# V1.net
KiCad netlist of a schematic drawn in Altium Designer
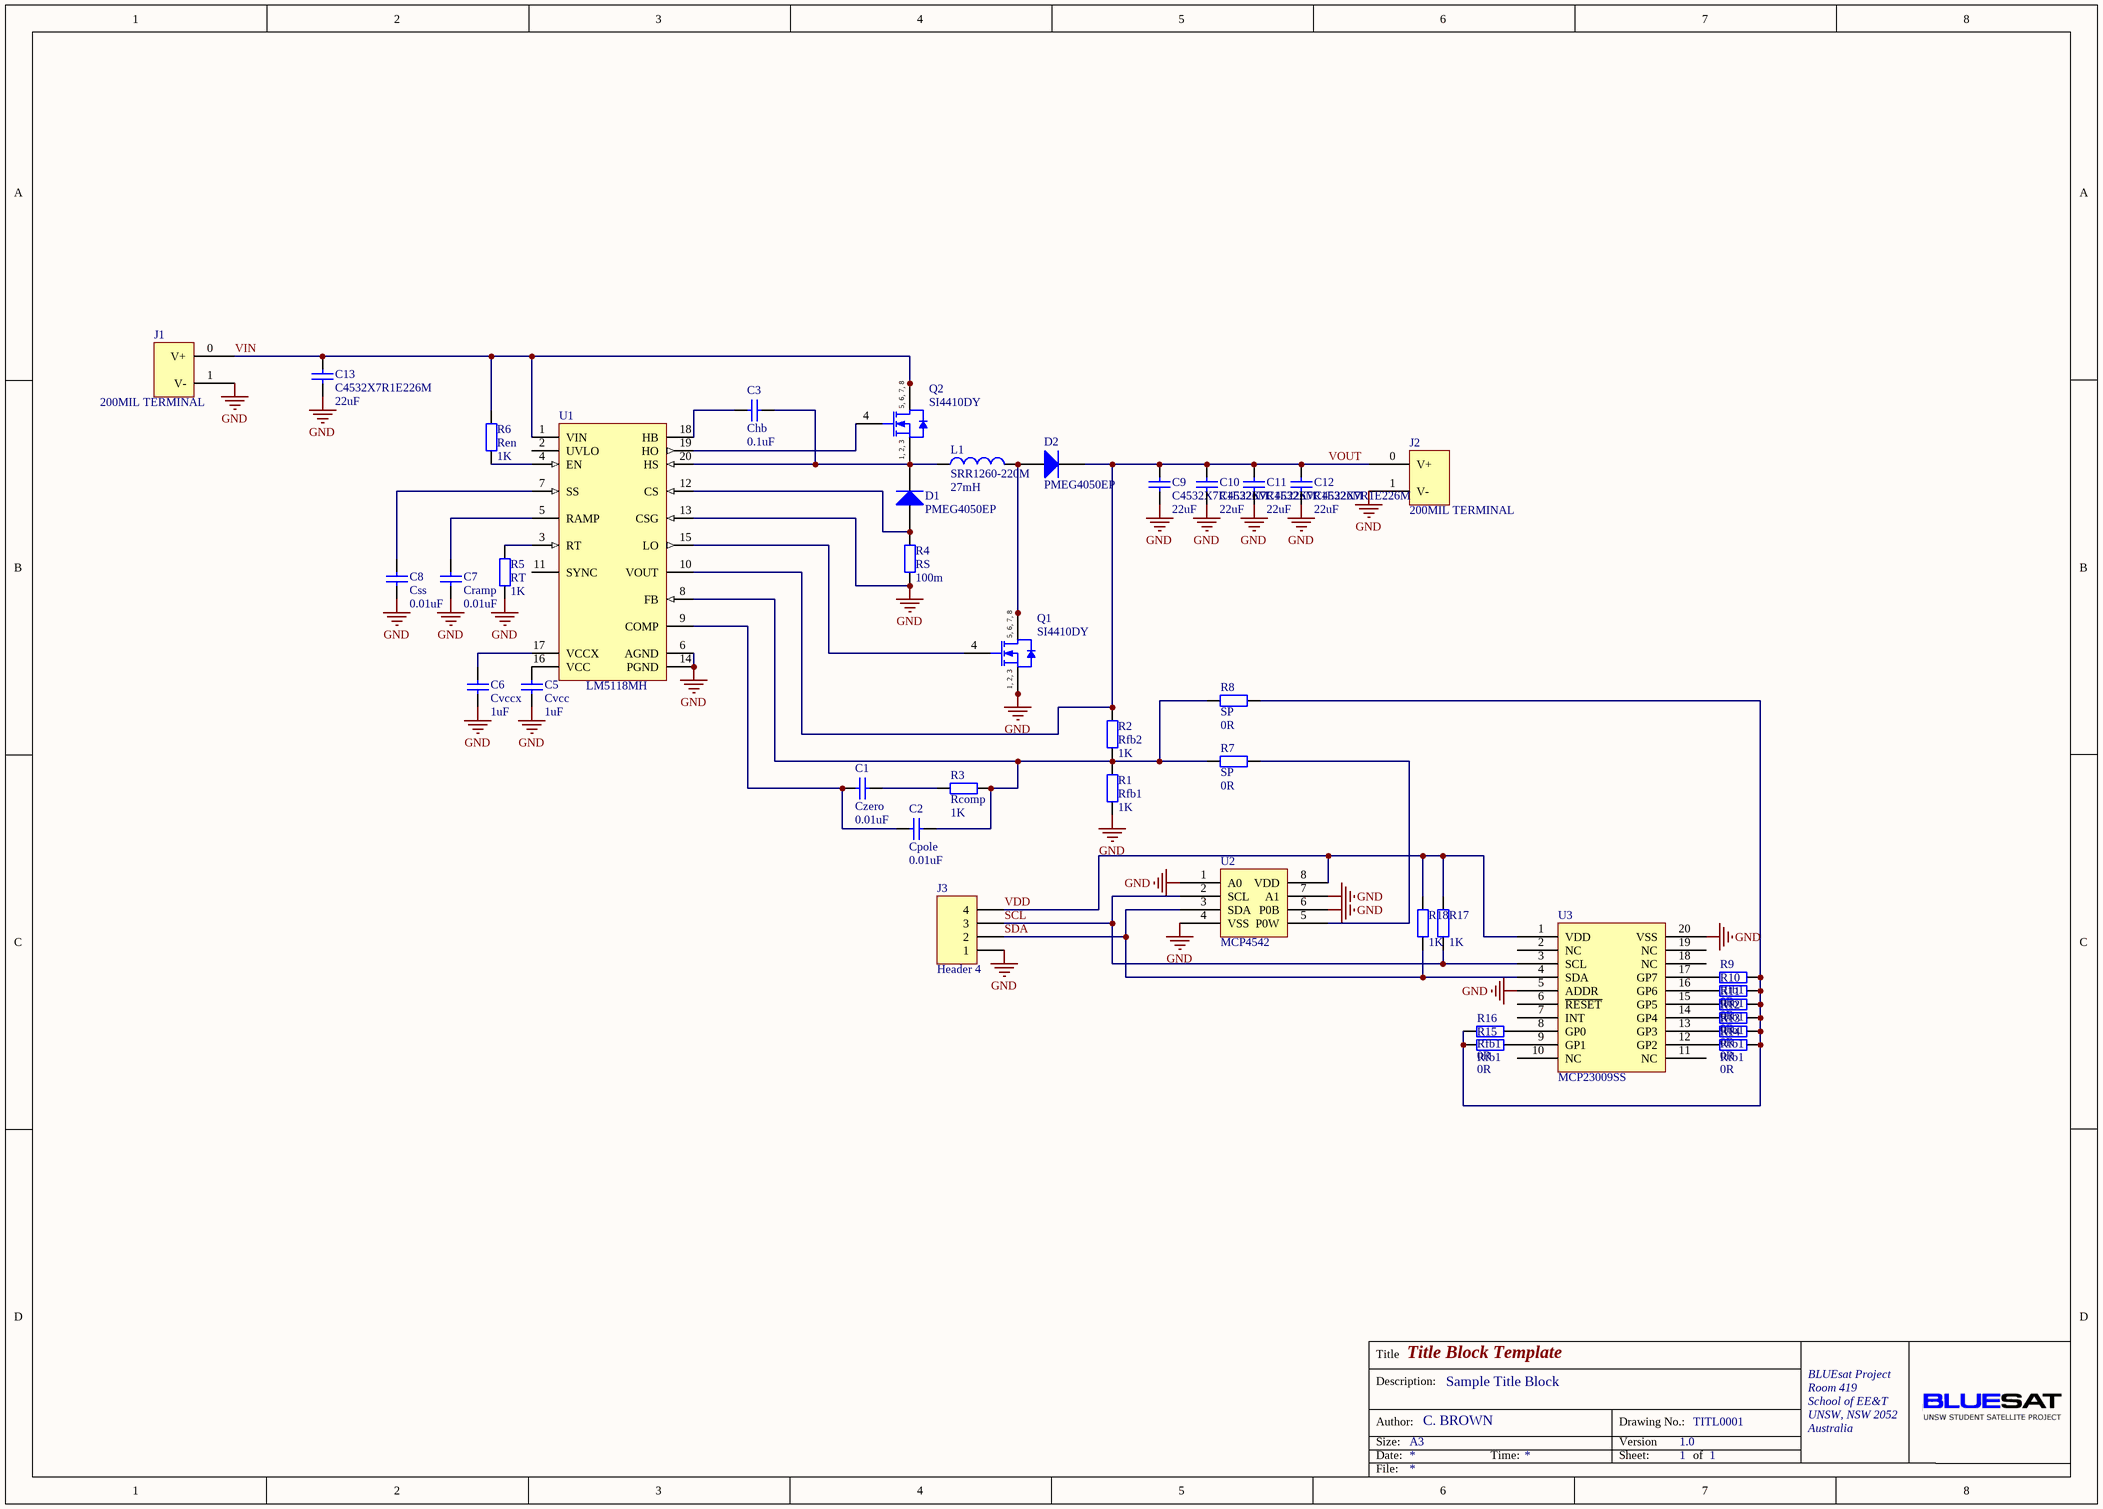
[diagram p0: V1.SchDoc]

(export (version "E")
  (design (tool "Eeschema 10.0.6"))
  (components
    (comp (ref "C1")
      (value "Czero")
      (footprint "R0805M")
      (description "Capacitor")
      (fields (field (name "ALTIUM_VALUE") "0.01uF") (field (name "PUBLISHER") "Altium Limited"))
      (libsource (lib "Miscellaneous Devices") (part "Cap"))
    )
    (comp (ref "C2")
      (value "Cpole")
      (footprint "R0805M")
      (description "Capacitor")
      (fields (field (name "ALTIUM_VALUE") "0.01uF") (field (name "PUBLISHER") "Altium Limited"))
      (libsource (lib "Miscellaneous Devices") (part "Cap"))
    )
    (comp (ref "C3")
      (value "Chb")
      (footprint "R0805M")
      (description "Capacitor")
      (fields (field (name "ALTIUM_VALUE") "0.1uF") (field (name "PUBLISHER") "Altium Limited"))
      (libsource (lib "Miscellaneous Devices") (part "Cap"))
    )
    (comp (ref "C5")
      (value "Cvcc")
      (footprint "R0805M")
      (description "Capacitor")
      (fields (field (name "ALTIUM_VALUE") "1uF") (field (name "PUBLISHER") "Altium Limited"))
      (libsource (lib "Miscellaneous Devices") (part "Cap"))
    )
    (comp (ref "C6")
      (value "Cvccx")
      (footprint "R0805M")
      (description "Capacitor")
      (fields (field (name "ALTIUM_VALUE") "1uF") (field (name "PUBLISHER") "Altium Limited"))
      (libsource (lib "Miscellaneous Devices") (part "Cap"))
    )
    (comp (ref "C7")
      (value "Cramp")
      (footprint "R0805M")
      (description "Capacitor")
      (fields (field (name "ALTIUM_VALUE") "0.01uF") (field (name "PUBLISHER") "Altium Limited"))
      (libsource (lib "Miscellaneous Devices") (part "Cap"))
    )
    (comp (ref "C8")
      (value "Css")
      (footprint "R0805M")
      (description "Capacitor")
      (fields (field (name "ALTIUM_VALUE") "0.01uF") (field (name "PUBLISHER") "Altium Limited"))
      (libsource (lib "Miscellaneous Devices") (part "Cap"))
    )
    (comp (ref "C9")
      (value "C4532X7R1E226M")
      (footprint "R1812M")
      (description "Capacitor")
      (fields (field (name "ALTIUM_VALUE") "22uF") (field (name "PUBLISHER") "Altium Limited"))
      (libsource (lib "Miscellaneous Devices") (part "Cap"))
    )
    (comp (ref "C10")
      (value "C4532X7R1E226M")
      (footprint "R1812M")
      (description "Capacitor")
      (fields (field (name "ALTIUM_VALUE") "22uF") (field (name "PUBLISHER") "Altium Limited"))
      (libsource (lib "Miscellaneous Devices") (part "Cap"))
    )
    (comp (ref "C11")
      (value "C4532X7R1E226M")
      (footprint "R1812M")
      (description "Capacitor")
      (fields (field (name "ALTIUM_VALUE") "22uF") (field (name "PUBLISHER") "Altium Limited"))
      (libsource (lib "Miscellaneous Devices") (part "Cap"))
    )
    (comp (ref "C12")
      (value "C4532X7R1E226M")
      (footprint "R1812M")
      (description "Capacitor")
      (fields (field (name "ALTIUM_VALUE") "22uF") (field (name "PUBLISHER") "Altium Limited"))
      (libsource (lib "Miscellaneous Devices") (part "Cap"))
    )
    (comp (ref "C13")
      (value "C4532X7R1E226M")
      (footprint "R1812M")
      (description "Capacitor")
      (fields (field (name "ALTIUM_VALUE") "22uF") (field (name "PUBLISHER") "Altium Limited"))
      (libsource (lib "Miscellaneous Devices") (part "Cap"))
    )
    (comp (ref "D1")
      (value "PMEG4050EP")
      (footprint "SOD128M")
      (description "Default Diode")
      (fields (field (name "PUBLISHER") "Altium Limited"))
      (libsource (lib "Miscellaneous Devices") (part "Diode"))
    )
    (comp (ref "D2")
      (value "PMEG4050EP")
      (footprint "SOD128M")
      (description "Default Diode")
      (fields (field (name "PUBLISHER") "Altium Limited"))
      (libsource (lib "Miscellaneous Devices") (part "Diode"))
    )
    (comp (ref "J1")
      (value "200MIL TERMINAL")
      (footprint "200MIL TERMINAL")
      (libsource (lib "VarReg") (part "200MIL TERMINAL"))
    )
    (comp (ref "J2")
      (value "200MIL TERMINAL")
      (footprint "200MIL TERMINAL")
      (libsource (lib "") (part "200MIL TERMINAL_1"))
    )
    (comp (ref "J3")
      (value "Header 4")
      (footprint "HDR1X4")
      (description "Header, 4-Pin")
      (fields (field (name "PUBLISHER") "Altium Limited"))
      (libsource (lib "Miscellaneous Connectors") (part "Header 4"))
    )
    (comp (ref "L1")
      (value "SRR1260-220M")
      (footprint "SRR1260M")
      (description "Inductor")
      (fields (field (name "ALTIUM_VALUE") "27mH") (field (name "PUBLISHER") "Altium Limited"))
      (libsource (lib "Miscellaneous Devices") (part "Inductor"))
    )
    (comp (ref "Q1")
      (value "SI4410DY")
      (footprint "SO-8_N")
      (description "N-Channel 30V (D-S)  MOSFET")
      (fields (field (name "PUBLISHER") "Altium Limited"))
      (libsource (lib "Vishay Siliconix Discrete MOSFET") (part "SI4410DY"))
    )
    (comp (ref "Q2")
      (value "SI4410DY")
      (footprint "SO-8_N")
      (description "N-Channel 30V (D-S)  MOSFET")
      (fields (field (name "PUBLISHER") "Altium Limited"))
      (libsource (lib "Vishay Siliconix Discrete MOSFET") (part "SI4410DY"))
    )
    (comp (ref "R1")
      (value "Rfb1")
      (footprint "R0805M")
      (description "Resistor")
      (fields (field (name "ALTIUM_VALUE") "1K") (field (name "PUBLISHER") "Altium Limited"))
      (libsource (lib "") (part "Res2_2"))
    )
    (comp (ref "R2")
      (value "Rfb2")
      (footprint "R0805M")
      (description "Resistor")
      (fields (field (name "ALTIUM_VALUE") "1K") (field (name "PUBLISHER") "Altium Limited"))
      (libsource (lib "") (part "Res2_2"))
    )
    (comp (ref "R3")
      (value "Rcomp")
      (footprint "R0805M")
      (description "Resistor")
      (fields (field (name "ALTIUM_VALUE") "1K") (field (name "PUBLISHER") "Altium Limited"))
      (libsource (lib "") (part "Res2_1"))
    )
    (comp (ref "R4")
      (value "RS")
      (footprint "R0805M")
      (description "Resistor")
      (fields (field (name "ALTIUM_VALUE") "100m") (field (name "PUBLISHER") "Altium Limited"))
      (libsource (lib "") (part "Res2_2"))
    )
    (comp (ref "R5")
      (value "RT")
      (footprint "R0805M")
      (description "Resistor")
      (fields (field (name "ALTIUM_VALUE") "1K") (field (name "PUBLISHER") "Altium Limited"))
      (libsource (lib "") (part "Res2_2"))
    )
    (comp (ref "R6")
      (value "Ren")
      (footprint "R0805M")
      (description "Resistor")
      (fields (field (name "ALTIUM_VALUE") "1K") (field (name "PUBLISHER") "Altium Limited"))
      (libsource (lib "") (part "Res2_2"))
    )
    (comp (ref "R7")
      (value "SP")
      (footprint "R0805M")
      (description "Resistor")
      (fields (field (name "ALTIUM_VALUE") "0R") (field (name "PUBLISHER") "Altium Limited"))
      (libsource (lib "Miscellaneous Devices") (part "Res2"))
    )
    (comp (ref "R8")
      (value "SP")
      (footprint "R0805M")
      (description "Resistor")
      (fields (field (name "ALTIUM_VALUE") "0R") (field (name "PUBLISHER") "Altium Limited"))
      (libsource (lib "Miscellaneous Devices") (part "Res2"))
    )
    (comp (ref "R9")
      (value "Rfb1")
      (footprint "R0805M")
      (description "Resistor")
      (fields (field (name "ALTIUM_VALUE") "0R") (field (name "PUBLISHER") "Altium Limited"))
      (libsource (lib "Miscellaneous Devices") (part "Res2"))
    )
    (comp (ref "R10")
      (value "Rfb1")
      (footprint "R0805M")
      (description "Resistor")
      (fields (field (name "ALTIUM_VALUE") "0R") (field (name "PUBLISHER") "Altium Limited"))
      (libsource (lib "Miscellaneous Devices") (part "Res2"))
    )
    (comp (ref "R11")
      (value "Rfb1")
      (footprint "R0805M")
      (description "Resistor")
      (fields (field (name "ALTIUM_VALUE") "0R") (field (name "PUBLISHER") "Altium Limited"))
      (libsource (lib "Miscellaneous Devices") (part "Res2"))
    )
    (comp (ref "R12")
      (value "Rfb1")
      (footprint "R0805M")
      (description "Resistor")
      (fields (field (name "ALTIUM_VALUE") "0R") (field (name "PUBLISHER") "Altium Limited"))
      (libsource (lib "Miscellaneous Devices") (part "Res2"))
    )
    (comp (ref "R13")
      (value "Rfb1")
      (footprint "R0805M")
      (description "Resistor")
      (fields (field (name "ALTIUM_VALUE") "0R") (field (name "PUBLISHER") "Altium Limited"))
      (libsource (lib "Miscellaneous Devices") (part "Res2"))
    )
    (comp (ref "R14")
      (value "Rfb1")
      (footprint "R0805M")
      (description "Resistor")
      (fields (field (name "ALTIUM_VALUE") "0R") (field (name "PUBLISHER") "Altium Limited"))
      (libsource (lib "Miscellaneous Devices") (part "Res2"))
    )
    (comp (ref "R15")
      (value "Rfb1")
      (footprint "R0805M")
      (description "Resistor")
      (fields (field (name "ALTIUM_VALUE") "0R") (field (name "PUBLISHER") "Altium Limited"))
      (libsource (lib "Miscellaneous Devices") (part "Res2"))
    )
    (comp (ref "R16")
      (value "Rfb1")
      (footprint "R0805M")
      (description "Resistor")
      (fields (field (name "ALTIUM_VALUE") "0R") (field (name "PUBLISHER") "Altium Limited"))
      (libsource (lib "Miscellaneous Devices") (part "Res2"))
    )
    (comp (ref "R17")
      (value "1K")
      (footprint "R0805M")
      (description "Resistor")
      (fields (field (name "PUBLISHER") "Altium Limited"))
      (libsource (lib "") (part "Res2_2"))
    )
    (comp (ref "R18")
      (value "1K")
      (footprint "R0805M")
      (description "Resistor")
      (fields (field (name "PUBLISHER") "Altium Limited"))
      (libsource (lib "") (part "Res2_2"))
    )
    (comp (ref "U1")
      (value "LM5118MH")
      (footprint "MXA20A_N")
      (description "Wide Voltage Range Buck-Boost Controller")
      (fields
        (field (name "MANUFACTURER") "National Semiconductor")
        (field (name "DIGIKEYPARTNUMBER") "LM5118MH-ND")
        (field (name "PUBLISHER") "Altium Limited")
      )
      (libsource (lib "NSC Switcher") (part "LM5118MH"))
    )
    (comp (ref "U2")
      (value "MCP4542")
      (footprint "Zetex Discrete MOSFET:MSOP8")
      (libsource (lib "VarReg") (part "MCP4542"))
    )
    (comp (ref "U3")
      (value "MCP23009SS")
      (footprint "SSOP20_M")
      (libsource (lib "VarReg") (part "MCP23009SS"))
    )
  )
  (nets
    (net (code "1") (name "/SCL") (class "Default")
      (node (ref "J3") (pin "3") (pinfunction "3_3") (pintype "passive"))
      (node (ref "R17") (pin "1") (pinfunction "1_1") (pintype "passive"))
      (node (ref "U2") (pin "2") (pinfunction "SCL_2") (pintype "passive"))
      (node (ref "U3") (pin "3") (pinfunction "SCL_3") (pintype "passive"))
    )
    (net (code "2") (name "/SDA") (class "Default")
      (node (ref "J3") (pin "2") (pinfunction "2_2") (pintype "passive"))
      (node (ref "R18") (pin "1") (pinfunction "1_1") (pintype "passive"))
      (node (ref "U2") (pin "3") (pinfunction "SDA_3") (pintype "passive"))
      (node (ref "U3") (pin "4") (pinfunction "SDA_4") (pintype "passive"))
    )
    (net (code "3") (name "/VDD") (class "Default")
      (node (ref "J3") (pin "4") (pinfunction "4_4") (pintype "passive"))
      (node (ref "R17") (pin "2") (pinfunction "2_2") (pintype "passive"))
      (node (ref "R18") (pin "2") (pinfunction "2_2") (pintype "passive"))
      (node (ref "U2") (pin "8") (pinfunction "VDD_8") (pintype "passive"))
      (node (ref "U3") (pin "1") (pinfunction "VDD_1") (pintype "passive"))
    )
    (net (code "4") (name "/VIN") (class "Default")
      (node (ref "C13") (pin "2") (pinfunction "2_2") (pintype "passive"))
      (node (ref "J1") (pin "0") (pinfunction "V+_0") (pintype "passive"))
      (node (ref "Q2") (pin "5") (pinfunction "D_5") (pintype "passive"))
      (node (ref "Q2") (pin "6") (pinfunction "D_6") (pintype "passive"))
      (node (ref "Q2") (pin "7") (pinfunction "D_7") (pintype "passive"))
      (node (ref "Q2") (pin "8") (pinfunction "D_8") (pintype "passive"))
      (node (ref "R6") (pin "2") (pinfunction "2_2") (pintype "passive"))
      (node (ref "U1") (pin "1") (pinfunction "VIN_1") (pintype "power_in"))
    )
    (net (code "5") (name "/VOUT") (class "Default")
      (node (ref "C10") (pin "2") (pinfunction "2_2") (pintype "passive"))
      (node (ref "C11") (pin "2") (pinfunction "2_2") (pintype "passive"))
      (node (ref "C12") (pin "2") (pinfunction "2_2") (pintype "passive"))
      (node (ref "C9") (pin "2") (pinfunction "2_2") (pintype "passive"))
      (node (ref "D2") (pin "2") (pinfunction "K_2") (pintype "passive"))
      (node (ref "J2") (pin "0") (pinfunction "V+_0") (pintype "passive"))
      (node (ref "R2") (pin "2") (pinfunction "2_2") (pintype "passive"))
      (node (ref "U1") (pin "10") (pinfunction "VOUT_10") (pintype "passive"))
    )
    (net (code "6") (name "GND") (class "Default")
      (node (ref "C10") (pin "1") (pinfunction "1_1") (pintype "passive"))
      (node (ref "C11") (pin "1") (pinfunction "1_1") (pintype "passive"))
      (node (ref "C12") (pin "1") (pinfunction "1_1") (pintype "passive"))
      (node (ref "C13") (pin "1") (pinfunction "1_1") (pintype "passive"))
      (node (ref "C5") (pin "1") (pinfunction "1_1") (pintype "passive"))
      (node (ref "C6") (pin "1") (pinfunction "1_1") (pintype "passive"))
      (node (ref "C7") (pin "1") (pinfunction "1_1") (pintype "passive"))
      (node (ref "C8") (pin "1") (pinfunction "1_1") (pintype "passive"))
      (node (ref "C9") (pin "1") (pinfunction "1_1") (pintype "passive"))
      (node (ref "J1") (pin "1") (pinfunction "V-_1") (pintype "passive"))
      (node (ref "J2") (pin "1") (pinfunction "V-_1") (pintype "passive"))
      (node (ref "J3") (pin "1") (pinfunction "1_1") (pintype "passive"))
      (node (ref "Q1") (pin "1") (pinfunction "S_1") (pintype "passive"))
      (node (ref "Q1") (pin "2") (pinfunction "S_2") (pintype "passive"))
      (node (ref "Q1") (pin "3") (pinfunction "S_3") (pintype "passive"))
      (node (ref "R1") (pin "1") (pinfunction "1_1") (pintype "passive"))
      (node (ref "R4") (pin "1") (pinfunction "1_1") (pintype "passive"))
      (node (ref "R5") (pin "1") (pinfunction "1_1") (pintype "passive"))
      (node (ref "U1") (pin "13") (pinfunction "CSG_13") (pintype "input"))
      (node (ref "U1") (pin "14") (pinfunction "PGND_14") (pintype "power_in"))
      (node (ref "U1") (pin "6") (pinfunction "AGND_6") (pintype "power_in"))
      (node (ref "U2") (pin "1") (pinfunction "A0_1") (pintype "passive"))
      (node (ref "U2") (pin "4") (pinfunction "VSS_4") (pintype "passive"))
      (node (ref "U2") (pin "6") (pinfunction "P0B_6") (pintype "passive"))
      (node (ref "U2") (pin "7") (pinfunction "A1_7") (pintype "passive"))
      (node (ref "U3") (pin "20") (pinfunction "VSS_20") (pintype "passive"))
      (node (ref "U3") (pin "5") (pinfunction "ADDR_5") (pintype "passive"))
    )
    (net (code "7") (name "Net-(C1-Pad2)") (class "Default")
      (node (ref "C1") (pin "2") (pinfunction "2_2") (pintype "passive"))
      (node (ref "R3") (pin "1") (pinfunction "1_1") (pintype "passive"))
    )
    (net (code "8") (name "Net-(D1-A)") (class "Default")
      (node (ref "D1") (pin "1") (pinfunction "A_1") (pintype "passive"))
      (node (ref "R4") (pin "2") (pinfunction "2_2") (pintype "passive"))
      (node (ref "U1") (pin "12") (pinfunction "CS_12") (pintype "input"))
    )
    (net (code "9") (name "Net-(D1-K)") (class "Default")
      (node (ref "C3") (pin "2") (pinfunction "2_2") (pintype "passive"))
      (node (ref "D1") (pin "2") (pinfunction "K_2") (pintype "passive"))
      (node (ref "L1") (pin "1") (pinfunction "1_1") (pintype "passive"))
      (node (ref "Q2") (pin "1") (pinfunction "S_1") (pintype "passive"))
      (node (ref "Q2") (pin "2") (pinfunction "S_2") (pintype "passive"))
      (node (ref "Q2") (pin "3") (pinfunction "S_3") (pintype "passive"))
      (node (ref "U1") (pin "20") (pinfunction "HS_20") (pintype "input"))
    )
    (net (code "10") (name "Net-(D2-A)") (class "Default")
      (node (ref "D2") (pin "1") (pinfunction "A_1") (pintype "passive"))
      (node (ref "L1") (pin "2") (pinfunction "2_2") (pintype "passive"))
      (node (ref "Q1") (pin "5") (pinfunction "D_5") (pintype "passive"))
      (node (ref "Q1") (pin "6") (pinfunction "D_6") (pintype "passive"))
      (node (ref "Q1") (pin "7") (pinfunction "D_7") (pintype "passive"))
      (node (ref "Q1") (pin "8") (pinfunction "D_8") (pintype "passive"))
    )
    (net (code "11") (name "Net-(Q1-G)") (class "Default")
      (node (ref "Q1") (pin "4") (pinfunction "G_4") (pintype "passive"))
      (node (ref "U1") (pin "15") (pinfunction "LO_15") (pintype "output"))
    )
    (net (code "12") (name "Net-(Q2-G)") (class "Default")
      (node (ref "Q2") (pin "4") (pinfunction "G_4") (pintype "passive"))
      (node (ref "U1") (pin "19") (pinfunction "HO_19") (pintype "output"))
    )
    (net (code "13") (name "Net-(R10-Pad1)") (class "Default")
      (node (ref "R10") (pin "1") (pinfunction "1_1") (pintype "passive"))
      (node (ref "R11") (pin "1") (pinfunction "1_1") (pintype "passive"))
      (node (ref "R12") (pin "1") (pinfunction "1_1") (pintype "passive"))
      (node (ref "R13") (pin "1") (pinfunction "1_1") (pintype "passive"))
      (node (ref "R14") (pin "1") (pinfunction "1_1") (pintype "passive"))
      (node (ref "R15") (pin "2") (pinfunction "2_2") (pintype "passive"))
      (node (ref "R16") (pin "2") (pinfunction "2_2") (pintype "passive"))
      (node (ref "R8") (pin "1") (pinfunction "1_1") (pintype "passive"))
      (node (ref "R9") (pin "1") (pinfunction "1_1") (pintype "passive"))
    )
    (net (code "14") (name "Net-(U1-COMP)") (class "Default")
      (node (ref "C1") (pin "1") (pinfunction "1_1") (pintype "passive"))
      (node (ref "C2") (pin "1") (pinfunction "1_1") (pintype "passive"))
      (node (ref "U1") (pin "9") (pinfunction "COMP_9") (pintype "passive"))
    )
    (net (code "15") (name "Net-(U1-EN)") (class "Default")
      (node (ref "R6") (pin "1") (pinfunction "1_1") (pintype "passive"))
      (node (ref "U1") (pin "4") (pinfunction "EN_4") (pintype "input"))
    )
    (net (code "16") (name "Net-(U1-FB)") (class "Default")
      (node (ref "C2") (pin "2") (pinfunction "2_2") (pintype "passive"))
      (node (ref "R1") (pin "2") (pinfunction "2_2") (pintype "passive"))
      (node (ref "R2") (pin "1") (pinfunction "1_1") (pintype "passive"))
      (node (ref "R3") (pin "2") (pinfunction "2_2") (pintype "passive"))
      (node (ref "R7") (pin "2") (pinfunction "2_2") (pintype "passive"))
      (node (ref "R8") (pin "2") (pinfunction "2_2") (pintype "passive"))
      (node (ref "U1") (pin "8") (pinfunction "FB_8") (pintype "input"))
    )
    (net (code "17") (name "Net-(U1-HB)") (class "Default")
      (node (ref "C3") (pin "1") (pinfunction "1_1") (pintype "passive"))
      (node (ref "U1") (pin "18") (pinfunction "HB_18") (pintype "passive"))
    )
    (net (code "18") (name "Net-(U1-RAMP)") (class "Default")
      (node (ref "C7") (pin "2") (pinfunction "2_2") (pintype "passive"))
      (node (ref "U1") (pin "5") (pinfunction "RAMP_5") (pintype "passive"))
    )
    (net (code "19") (name "Net-(U1-RT)") (class "Default")
      (node (ref "R5") (pin "2") (pinfunction "2_2") (pintype "passive"))
      (node (ref "U1") (pin "3") (pinfunction "RT_3") (pintype "input"))
    )
    (net (code "20") (name "Net-(U1-SS)") (class "Default")
      (node (ref "C8") (pin "2") (pinfunction "2_2") (pintype "passive"))
      (node (ref "U1") (pin "7") (pinfunction "SS_7") (pintype "input"))
    )
    (net (code "21") (name "Net-(U1-VCC)") (class "Default")
      (node (ref "C5") (pin "2") (pinfunction "2_2") (pintype "passive"))
      (node (ref "U1") (pin "16") (pinfunction "VCC_16") (pintype "power_in"))
    )
    (net (code "22") (name "Net-(U1-VCCX)") (class "Default")
      (node (ref "C6") (pin "2") (pinfunction "2_2") (pintype "passive"))
      (node (ref "U1") (pin "17") (pinfunction "VCCX_17") (pintype "power_in"))
    )
    (net (code "23") (name "Net-(U2-P0W)") (class "Default")
      (node (ref "R7") (pin "1") (pinfunction "1_1") (pintype "passive"))
      (node (ref "U2") (pin "5") (pinfunction "P0W_5") (pintype "passive"))
    )
    (net (code "24") (name "Net-(U3-GP0)") (class "Default")
      (node (ref "R16") (pin "1") (pinfunction "1_1") (pintype "passive"))
      (node (ref "U3") (pin "8") (pinfunction "GP0_8") (pintype "passive"))
    )
    (net (code "25") (name "Net-(U3-GP1)") (class "Default")
      (node (ref "R15") (pin "1") (pinfunction "1_1") (pintype "passive"))
      (node (ref "U3") (pin "9") (pinfunction "GP1_9") (pintype "passive"))
    )
    (net (code "26") (name "Net-(U3-GP2)") (class "Default")
      (node (ref "R14") (pin "2") (pinfunction "2_2") (pintype "passive"))
      (node (ref "U3") (pin "12") (pinfunction "GP2_12") (pintype "passive"))
    )
    (net (code "27") (name "Net-(U3-GP3)") (class "Default")
      (node (ref "R13") (pin "2") (pinfunction "2_2") (pintype "passive"))
      (node (ref "U3") (pin "13") (pinfunction "GP3_13") (pintype "passive"))
    )
    (net (code "28") (name "Net-(U3-GP4)") (class "Default")
      (node (ref "R12") (pin "2") (pinfunction "2_2") (pintype "passive"))
      (node (ref "U3") (pin "14") (pinfunction "GP4_14") (pintype "passive"))
    )
    (net (code "29") (name "Net-(U3-GP5)") (class "Default")
      (node (ref "R11") (pin "2") (pinfunction "2_2") (pintype "passive"))
      (node (ref "U3") (pin "15") (pinfunction "GP5_15") (pintype "passive"))
    )
    (net (code "30") (name "Net-(U3-GP6)") (class "Default")
      (node (ref "R10") (pin "2") (pinfunction "2_2") (pintype "passive"))
      (node (ref "U3") (pin "16") (pinfunction "GP6_16") (pintype "passive"))
    )
    (net (code "31") (name "Net-(U3-GP7)") (class "Default")
      (node (ref "R9") (pin "2") (pinfunction "2_2") (pintype "passive"))
      (node (ref "U3") (pin "17") (pinfunction "GP7_17") (pintype "passive"))
    )
    (net (code "32") (name "unconnected-(U1-SYNC-Pad11)") (class "Default")
      (node (ref "U1") (pin "11") (pinfunction "SYNC_11") (pintype "passive"))
    )
    (net (code "33") (name "unconnected-(U1-UVLO-Pad2)") (class "Default")
      (node (ref "U1") (pin "2") (pinfunction "UVLO_2") (pintype "passive"))
    )
    (net (code "34") (name "unconnected-(U3-INT-Pad7)") (class "Default")
      (node (ref "U3") (pin "7") (pinfunction "INT_7") (pintype "passive"))
    )
    (net (code "35") (name "unconnected-(U3-NC-Pad2)") (class "Default")
      (node (ref "U3") (pin "2") (pinfunction "NC_2") (pintype "passive"))
    )
    (net (code "36") (name "unconnected-(U3-NC-Pad10)") (class "Default")
      (node (ref "U3") (pin "10") (pinfunction "NC_10") (pintype "passive"))
    )
    (net (code "37") (name "unconnected-(U3-NC-Pad11)") (class "Default")
      (node (ref "U3") (pin "11") (pinfunction "NC_11") (pintype "passive"))
    )
    (net (code "38") (name "unconnected-(U3-NC-Pad18)") (class "Default")
      (node (ref "U3") (pin "18") (pinfunction "NC_18") (pintype "passive"))
    )
    (net (code "39") (name "unconnected-(U3-NC-Pad19)") (class "Default")
      (node (ref "U3") (pin "19") (pinfunction "NC_19") (pintype "passive"))
    )
    (net (code "40") (name "unconnected-(U3-~{RESET}-Pad6)") (class "Default")
      (node (ref "U3") (pin "6") (pinfunction "~{RESET}_6") (pintype "passive"))
    )
  )
)
